# PiMometer.net
KiCad netlist of a schematic drawn in EAGLE
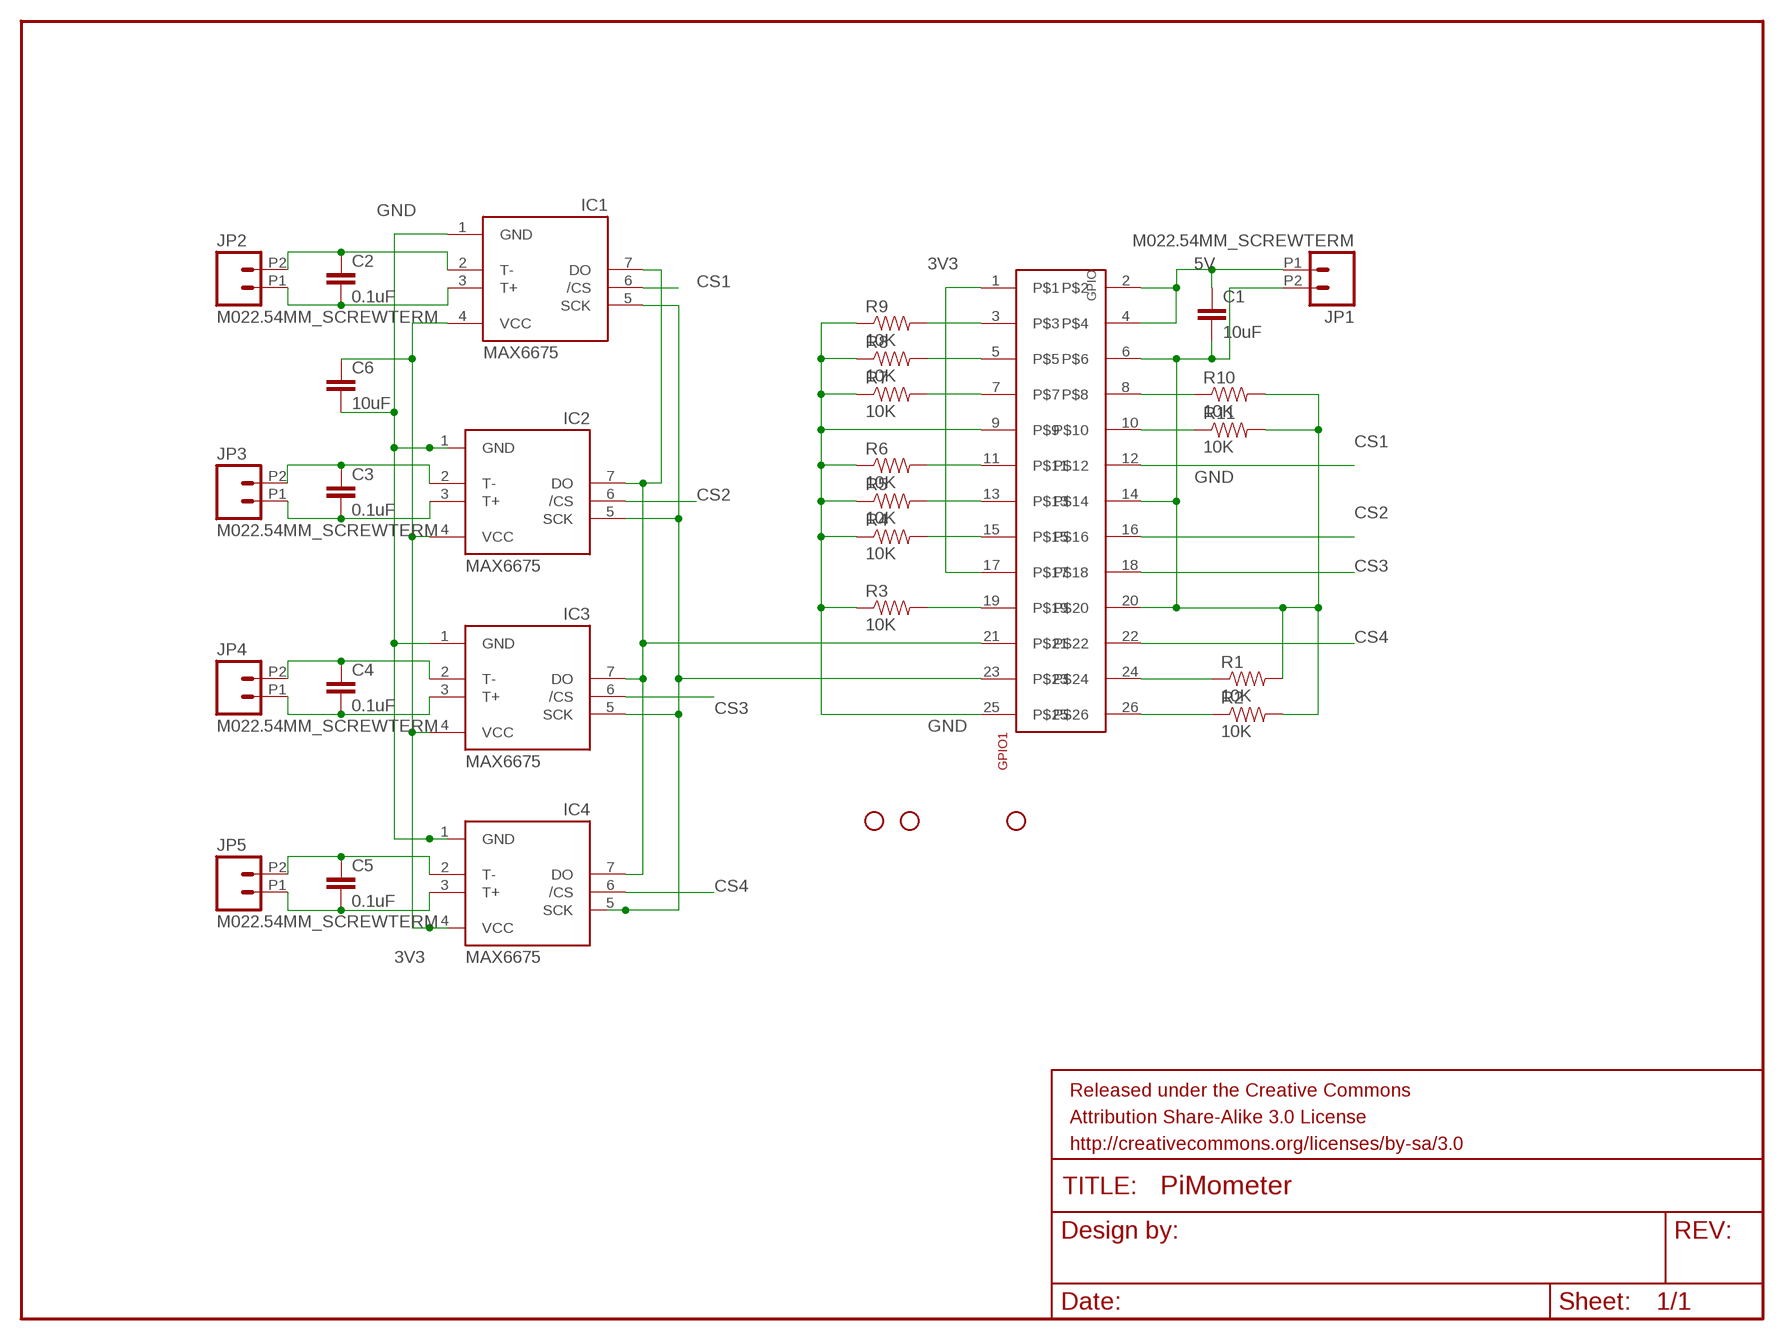
[diagram p0: schematic, sheet 1]

(export (version "E")
  (design (tool "Eeschema 10.0.6"))
  (components
    (comp (ref "C1")
      (value "10uF")
      (footprint "eagle-import:1210")
      (libsource (lib "eagle-import") (part "10UF50V20%(1210)"))
    )
    (comp (ref "C2")
      (value "0.1uF")
      (footprint "eagle-import:0603-CAP")
      (libsource (lib "eagle-import") (part "0.1UF-100V-10%(0603)"))
    )
    (comp (ref "C3")
      (value "0.1uF")
      (footprint "eagle-import:0603-CAP")
      (libsource (lib "eagle-import") (part "0.1UF-100V-10%(0603)"))
    )
    (comp (ref "C4")
      (value "0.1uF")
      (footprint "eagle-import:0603-CAP")
      (libsource (lib "eagle-import") (part "0.1UF-100V-10%(0603)"))
    )
    (comp (ref "C5")
      (value "0.1uF")
      (footprint "eagle-import:0603-CAP")
      (libsource (lib "eagle-import") (part "0.1UF-100V-10%(0603)"))
    )
    (comp (ref "C6")
      (value "10uF")
      (footprint "eagle-import:1210")
      (libsource (lib "eagle-import") (part "10UF50V20%(1210)"))
    )
    (comp (ref "FRAME1")
      (value "FRAME-LETTER")
      (footprint "eagle-import:CREATIVE_COMMONS")
      (libsource (lib "eagle-import") (part "FRAME-LETTER"))
    )
    (comp (ref "GPIO1")
      (value "2X132X13")
      (footprint "eagle-import:2X13")
      (libsource (lib "eagle-import") (part "2X132X13"))
    )
    (comp (ref "IC1")
      (value "MAX6675")
      (footprint "eagle-import:SO08")
      (libsource (lib "eagle-import") (part "MAX6675"))
    )
    (comp (ref "IC2")
      (value "MAX6675")
      (footprint "eagle-import:SO08")
      (libsource (lib "eagle-import") (part "MAX6675"))
    )
    (comp (ref "IC3")
      (value "MAX6675")
      (footprint "eagle-import:SO08")
      (libsource (lib "eagle-import") (part "MAX6675"))
    )
    (comp (ref "IC4")
      (value "MAX6675")
      (footprint "eagle-import:SO08")
      (libsource (lib "eagle-import") (part "MAX6675"))
    )
    (comp (ref "JP1")
      (value "M022.54MM_SCREWTERM")
      (footprint "eagle-import:1X02_2.54_SCREWTERM")
      (libsource (lib "eagle-import") (part "M022.54MM_SCREWTERM"))
    )
    (comp (ref "JP2")
      (value "M022.54MM_SCREWTERM")
      (footprint "eagle-import:1X02_2.54_SCREWTERM")
      (libsource (lib "eagle-import") (part "M022.54MM_SCREWTERM"))
    )
    (comp (ref "JP3")
      (value "M022.54MM_SCREWTERM")
      (footprint "eagle-import:1X02_2.54_SCREWTERM")
      (libsource (lib "eagle-import") (part "M022.54MM_SCREWTERM"))
    )
    (comp (ref "JP4")
      (value "M022.54MM_SCREWTERM")
      (footprint "eagle-import:1X02_2.54_SCREWTERM")
      (libsource (lib "eagle-import") (part "M022.54MM_SCREWTERM"))
    )
    (comp (ref "JP5")
      (value "M022.54MM_SCREWTERM")
      (footprint "eagle-import:1X02_2.54_SCREWTERM")
      (libsource (lib "eagle-import") (part "M022.54MM_SCREWTERM"))
    )
    (comp (ref "R1")
      (value "10K")
      (footprint "eagle-import:0603-RES")
      (libsource (lib "eagle-import") (part "10KOHM1/10W1%(0603)0603"))
    )
    (comp (ref "R2")
      (value "10K")
      (footprint "eagle-import:0603-RES")
      (libsource (lib "eagle-import") (part "10KOHM1/10W1%(0603)0603"))
    )
    (comp (ref "R3")
      (value "10K")
      (footprint "eagle-import:0603-RES")
      (libsource (lib "eagle-import") (part "10KOHM1/10W1%(0603)0603"))
    )
    (comp (ref "R4")
      (value "10K")
      (footprint "eagle-import:0603-RES")
      (libsource (lib "eagle-import") (part "10KOHM1/10W1%(0603)0603"))
    )
    (comp (ref "R5")
      (value "10K")
      (footprint "eagle-import:0603-RES")
      (libsource (lib "eagle-import") (part "10KOHM1/10W1%(0603)0603"))
    )
    (comp (ref "R6")
      (value "10K")
      (footprint "eagle-import:0603-RES")
      (libsource (lib "eagle-import") (part "10KOHM1/10W1%(0603)0603"))
    )
    (comp (ref "R7")
      (value "10K")
      (footprint "eagle-import:0603-RES")
      (libsource (lib "eagle-import") (part "10KOHM1/10W1%(0603)0603"))
    )
    (comp (ref "R8")
      (value "10K")
      (footprint "eagle-import:0603-RES")
      (libsource (lib "eagle-import") (part "10KOHM1/10W1%(0603)0603"))
    )
    (comp (ref "R9")
      (value "10K")
      (footprint "eagle-import:0603-RES")
      (libsource (lib "eagle-import") (part "10KOHM1/10W1%(0603)0603"))
    )
    (comp (ref "R10")
      (value "10K")
      (footprint "eagle-import:0603-RES")
      (libsource (lib "eagle-import") (part "10KOHM1/10W1%(0603)0603"))
    )
    (comp (ref "R11")
      (value "10K")
      (footprint "eagle-import:0603-RES")
      (libsource (lib "eagle-import") (part "10KOHM1/10W1%(0603)0603"))
    )
    (comp (ref "STANDOFF1")
      (value "STAND-OFF")
      (footprint "eagle-import:STAND-OFF")
      (libsource (lib "eagle-import") (part "STAND-OFF"))
    )
    (comp (ref "STANDOFF2")
      (value "STAND-OFF")
      (footprint "eagle-import:STAND-OFF")
      (libsource (lib "eagle-import") (part "STAND-OFF"))
    )
    (comp (ref "STANDOFF4")
      (value "STAND-OFF")
      (footprint "eagle-import:STAND-OFF")
      (libsource (lib "eagle-import") (part "STAND-OFF"))
    )
  )
  (nets
    (net (code "1") (name "/3V3") (class "Default")
      (node (ref "C6") (pin "1") (pinfunction "1_1") (pintype "passive"))
      (node (ref "GPIO1") (pin "1") (pinfunction "P$1_1") (pintype "bidirectional"))
      (node (ref "GPIO1") (pin "17") (pinfunction "P$17_17") (pintype "bidirectional"))
      (node (ref "IC1") (pin "4") (pinfunction "VCC_4") (pintype "power_in"))
      (node (ref "IC2") (pin "4") (pinfunction "VCC_4") (pintype "power_in"))
      (node (ref "IC3") (pin "4") (pinfunction "VCC_4") (pintype "power_in"))
      (node (ref "IC4") (pin "4") (pinfunction "VCC_4") (pintype "power_in"))
    )
    (net (code "2") (name "/5V") (class "Default")
      (node (ref "C1") (pin "1") (pinfunction "1_1") (pintype "passive"))
      (node (ref "GPIO1") (pin "2") (pinfunction "P$2_2") (pintype "bidirectional"))
      (node (ref "GPIO1") (pin "4") (pinfunction "P$4_4") (pintype "bidirectional"))
      (node (ref "JP1") (pin "P1") (pinfunction "1_P1") (pintype "passive"))
    )
    (net (code "3") (name "/CS1") (class "Default")
      (node (ref "GPIO1") (pin "12") (pinfunction "P$12_12") (pintype "bidirectional"))
      (node (ref "IC1") (pin "6") (pinfunction "/CS_6") (pintype "input"))
    )
    (net (code "4") (name "/CS2") (class "Default")
      (node (ref "GPIO1") (pin "16") (pinfunction "P$16_16") (pintype "bidirectional"))
      (node (ref "IC2") (pin "6") (pinfunction "/CS_6") (pintype "input"))
    )
    (net (code "5") (name "/CS3") (class "Default")
      (node (ref "GPIO1") (pin "18") (pinfunction "P$18_18") (pintype "bidirectional"))
      (node (ref "IC3") (pin "6") (pinfunction "/CS_6") (pintype "input"))
    )
    (net (code "6") (name "/CS4") (class "Default")
      (node (ref "GPIO1") (pin "22") (pinfunction "P$22_22") (pintype "bidirectional"))
      (node (ref "IC4") (pin "6") (pinfunction "/CS_6") (pintype "input"))
    )
    (net (code "7") (name "/GND") (class "Default")
      (node (ref "C1") (pin "2") (pinfunction "2_2") (pintype "passive"))
      (node (ref "C6") (pin "2") (pinfunction "2_2") (pintype "passive"))
      (node (ref "GPIO1") (pin "14") (pinfunction "P$14_14") (pintype "bidirectional"))
      (node (ref "GPIO1") (pin "20") (pinfunction "P$20_20") (pintype "bidirectional"))
      (node (ref "GPIO1") (pin "25") (pinfunction "P$25_25") (pintype "bidirectional"))
      (node (ref "GPIO1") (pin "6") (pinfunction "P$6_6") (pintype "bidirectional"))
      (node (ref "GPIO1") (pin "9") (pinfunction "P$9_9") (pintype "bidirectional"))
      (node (ref "IC1") (pin "1") (pinfunction "GND_1") (pintype "power_in"))
      (node (ref "IC2") (pin "1") (pinfunction "GND_1") (pintype "power_in"))
      (node (ref "IC3") (pin "1") (pinfunction "GND_1") (pintype "power_in"))
      (node (ref "IC4") (pin "1") (pinfunction "GND_1") (pintype "power_in"))
      (node (ref "JP1") (pin "P2") (pinfunction "2_P2") (pintype "passive"))
      (node (ref "R1") (pin "2") (pinfunction "2_2") (pintype "passive"))
      (node (ref "R10") (pin "2") (pinfunction "2_2") (pintype "passive"))
      (node (ref "R11") (pin "2") (pinfunction "2_2") (pintype "passive"))
      (node (ref "R2") (pin "2") (pinfunction "2_2") (pintype "passive"))
      (node (ref "R3") (pin "1") (pinfunction "1_1") (pintype "passive"))
      (node (ref "R4") (pin "1") (pinfunction "1_1") (pintype "passive"))
      (node (ref "R5") (pin "1") (pinfunction "1_1") (pintype "passive"))
      (node (ref "R6") (pin "1") (pinfunction "1_1") (pintype "passive"))
      (node (ref "R7") (pin "1") (pinfunction "1_1") (pintype "passive"))
      (node (ref "R8") (pin "1") (pinfunction "1_1") (pintype "passive"))
      (node (ref "R9") (pin "1") (pinfunction "1_1") (pintype "passive"))
    )
    (net (code "8") (name "Net-(GPIO1-P$3)") (class "Default")
      (node (ref "GPIO1") (pin "3") (pinfunction "P$3_3") (pintype "bidirectional"))
      (node (ref "R9") (pin "2") (pinfunction "2_2") (pintype "passive"))
    )
    (net (code "9") (name "Net-(GPIO1-P$5)") (class "Default")
      (node (ref "GPIO1") (pin "5") (pinfunction "P$5_5") (pintype "bidirectional"))
      (node (ref "R8") (pin "2") (pinfunction "2_2") (pintype "passive"))
    )
    (net (code "10") (name "Net-(GPIO1-P$7)") (class "Default")
      (node (ref "GPIO1") (pin "7") (pinfunction "P$7_7") (pintype "bidirectional"))
      (node (ref "R7") (pin "2") (pinfunction "2_2") (pintype "passive"))
    )
    (net (code "11") (name "Net-(GPIO1-P$8)") (class "Default")
      (node (ref "GPIO1") (pin "8") (pinfunction "P$8_8") (pintype "bidirectional"))
      (node (ref "R10") (pin "1") (pinfunction "1_1") (pintype "passive"))
    )
    (net (code "12") (name "Net-(GPIO1-P$10)") (class "Default")
      (node (ref "GPIO1") (pin "10") (pinfunction "P$10_10") (pintype "bidirectional"))
      (node (ref "R11") (pin "1") (pinfunction "1_1") (pintype "passive"))
    )
    (net (code "13") (name "Net-(GPIO1-P$11)") (class "Default")
      (node (ref "GPIO1") (pin "11") (pinfunction "P$11_11") (pintype "bidirectional"))
      (node (ref "R6") (pin "2") (pinfunction "2_2") (pintype "passive"))
    )
    (net (code "14") (name "Net-(GPIO1-P$13)") (class "Default")
      (node (ref "GPIO1") (pin "13") (pinfunction "P$13_13") (pintype "bidirectional"))
      (node (ref "R5") (pin "2") (pinfunction "2_2") (pintype "passive"))
    )
    (net (code "15") (name "Net-(GPIO1-P$15)") (class "Default")
      (node (ref "GPIO1") (pin "15") (pinfunction "P$15_15") (pintype "bidirectional"))
      (node (ref "R4") (pin "2") (pinfunction "2_2") (pintype "passive"))
    )
    (net (code "16") (name "Net-(GPIO1-P$19)") (class "Default")
      (node (ref "GPIO1") (pin "19") (pinfunction "P$19_19") (pintype "bidirectional"))
      (node (ref "R3") (pin "2") (pinfunction "2_2") (pintype "passive"))
    )
    (net (code "17") (name "Net-(GPIO1-P$21)") (class "Default")
      (node (ref "GPIO1") (pin "21") (pinfunction "P$21_21") (pintype "bidirectional"))
      (node (ref "IC1") (pin "7") (pinfunction "DO_7") (pintype "output"))
      (node (ref "IC2") (pin "7") (pinfunction "DO_7") (pintype "output"))
      (node (ref "IC3") (pin "7") (pinfunction "DO_7") (pintype "output"))
      (node (ref "IC4") (pin "7") (pinfunction "DO_7") (pintype "output"))
    )
    (net (code "18") (name "Net-(GPIO1-P$23)") (class "Default")
      (node (ref "GPIO1") (pin "23") (pinfunction "P$23_23") (pintype "bidirectional"))
      (node (ref "IC1") (pin "5") (pinfunction "SCK_5") (pintype "input"))
      (node (ref "IC2") (pin "5") (pinfunction "SCK_5") (pintype "input"))
      (node (ref "IC3") (pin "5") (pinfunction "SCK_5") (pintype "input"))
      (node (ref "IC4") (pin "5") (pinfunction "SCK_5") (pintype "input"))
    )
    (net (code "19") (name "Net-(GPIO1-P$24)") (class "Default")
      (node (ref "GPIO1") (pin "24") (pinfunction "P$24_24") (pintype "bidirectional"))
      (node (ref "R1") (pin "1") (pinfunction "1_1") (pintype "passive"))
    )
    (net (code "20") (name "Net-(GPIO1-P$26)") (class "Default")
      (node (ref "GPIO1") (pin "26") (pinfunction "P$26_26") (pintype "bidirectional"))
      (node (ref "R2") (pin "1") (pinfunction "1_1") (pintype "passive"))
    )
    (net (code "21") (name "Net-(IC1-T+)") (class "Default")
      (node (ref "C2") (pin "2") (pinfunction "2_2") (pintype "passive"))
      (node (ref "IC1") (pin "3") (pinfunction "T+_3") (pintype "input"))
      (node (ref "JP2") (pin "P1") (pinfunction "1_P1") (pintype "passive"))
    )
    (net (code "22") (name "Net-(IC1-T-)") (class "Default")
      (node (ref "C2") (pin "1") (pinfunction "1_1") (pintype "passive"))
      (node (ref "IC1") (pin "2") (pinfunction "T-_2") (pintype "input"))
      (node (ref "JP2") (pin "P2") (pinfunction "2_P2") (pintype "passive"))
    )
    (net (code "23") (name "Net-(IC2-T+)") (class "Default")
      (node (ref "C3") (pin "2") (pinfunction "2_2") (pintype "passive"))
      (node (ref "IC2") (pin "3") (pinfunction "T+_3") (pintype "input"))
      (node (ref "JP3") (pin "P1") (pinfunction "1_P1") (pintype "passive"))
    )
    (net (code "24") (name "Net-(IC2-T-)") (class "Default")
      (node (ref "C3") (pin "1") (pinfunction "1_1") (pintype "passive"))
      (node (ref "IC2") (pin "2") (pinfunction "T-_2") (pintype "input"))
      (node (ref "JP3") (pin "P2") (pinfunction "2_P2") (pintype "passive"))
    )
    (net (code "25") (name "Net-(IC3-T+)") (class "Default")
      (node (ref "C4") (pin "2") (pinfunction "2_2") (pintype "passive"))
      (node (ref "IC3") (pin "3") (pinfunction "T+_3") (pintype "input"))
      (node (ref "JP4") (pin "P1") (pinfunction "1_P1") (pintype "passive"))
    )
    (net (code "26") (name "Net-(IC3-T-)") (class "Default")
      (node (ref "C4") (pin "1") (pinfunction "1_1") (pintype "passive"))
      (node (ref "IC3") (pin "2") (pinfunction "T-_2") (pintype "input"))
      (node (ref "JP4") (pin "P2") (pinfunction "2_P2") (pintype "passive"))
    )
    (net (code "27") (name "Net-(IC4-T+)") (class "Default")
      (node (ref "C5") (pin "2") (pinfunction "2_2") (pintype "passive"))
      (node (ref "IC4") (pin "3") (pinfunction "T+_3") (pintype "input"))
      (node (ref "JP5") (pin "P1") (pinfunction "1_P1") (pintype "passive"))
    )
    (net (code "28") (name "Net-(IC4-T-)") (class "Default")
      (node (ref "C5") (pin "1") (pinfunction "1_1") (pintype "passive"))
      (node (ref "IC4") (pin "2") (pinfunction "T-_2") (pintype "input"))
      (node (ref "JP5") (pin "P2") (pinfunction "2_P2") (pintype "passive"))
    )
  )
)
